# TTAmp_3T0K_Mechanical.net
KiCad netlist of a schematic drawn in Altium Designer
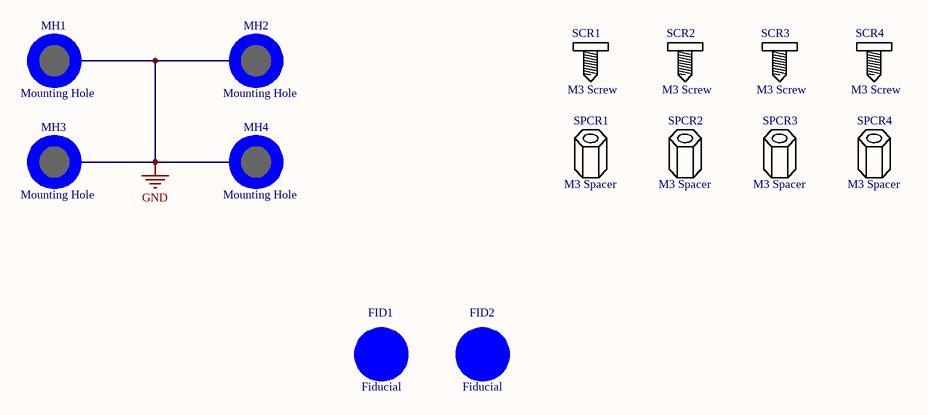
[diagram p0: TTAmp_3T0K_Mechanical.SchDoc]

(export (version "E")
  (design (tool "Eeschema 10.0.6"))
  (components
    (comp (ref "FID1") (value "Fiducial") (footprint "Fiducial") (libsource (lib "PCB") (part "FID")))
    (comp (ref "FID2") (value "Fiducial") (footprint "Fiducial") (libsource (lib "PCB") (part "FID")))
    (comp (ref "MH1")
      (value "Mounting Hole")
      (footprint "MH-M3_Copper")
      (description "M3 mounting hole")
      (libsource (lib "PCB") (part "MH"))
    )
    (comp (ref "MH2")
      (value "Mounting Hole")
      (footprint "MH-M3_Copper")
      (description "M3 mounting hole")
      (libsource (lib "PCB") (part "MH"))
    )
    (comp (ref "MH3")
      (value "Mounting Hole")
      (footprint "MH-M3_Copper")
      (description "M3 mounting hole")
      (libsource (lib "PCB") (part "MH"))
    )
    (comp (ref "MH4")
      (value "Mounting Hole")
      (footprint "MH-M3_Copper")
      (description "M3 mounting hole")
      (libsource (lib "PCB") (part "MH"))
    )
    (comp (ref "SCR1") (value "M3 Screw") (libsource (lib "Mechanical") (part "SCREW")))
    (comp (ref "SCR2") (value "M3 Screw") (libsource (lib "Mechanical") (part "SCREW")))
    (comp (ref "SCR3") (value "M3 Screw") (libsource (lib "Mechanical") (part "SCREW")))
    (comp (ref "SCR4") (value "M3 Screw") (libsource (lib "Mechanical") (part "SCREW")))
    (comp (ref "SPCR1") (value "M3 Spacer") (libsource (lib "Mechanical") (part "SPCR")))
    (comp (ref "SPCR2") (value "M3 Spacer") (libsource (lib "Mechanical") (part "SPCR")))
    (comp (ref "SPCR3") (value "M3 Spacer") (libsource (lib "Mechanical") (part "SPCR")))
    (comp (ref "SPCR4") (value "M3 Spacer") (libsource (lib "Mechanical") (part "SPCR")))
  )
  (nets
    (net (code "1") (name "GND") (class "Default")
      (node (ref "MH1") (pin "MH") (pinfunction "MH_MH") (pintype "passive"))
      (node (ref "MH2") (pin "MH") (pinfunction "MH_MH") (pintype "passive"))
      (node (ref "MH3") (pin "MH") (pinfunction "MH_MH") (pintype "passive"))
      (node (ref "MH4") (pin "MH") (pinfunction "MH_MH") (pintype "passive"))
    )
  )
)
